# USB_C.net
KiCad netlist of a schematic drawn in Altium Designer
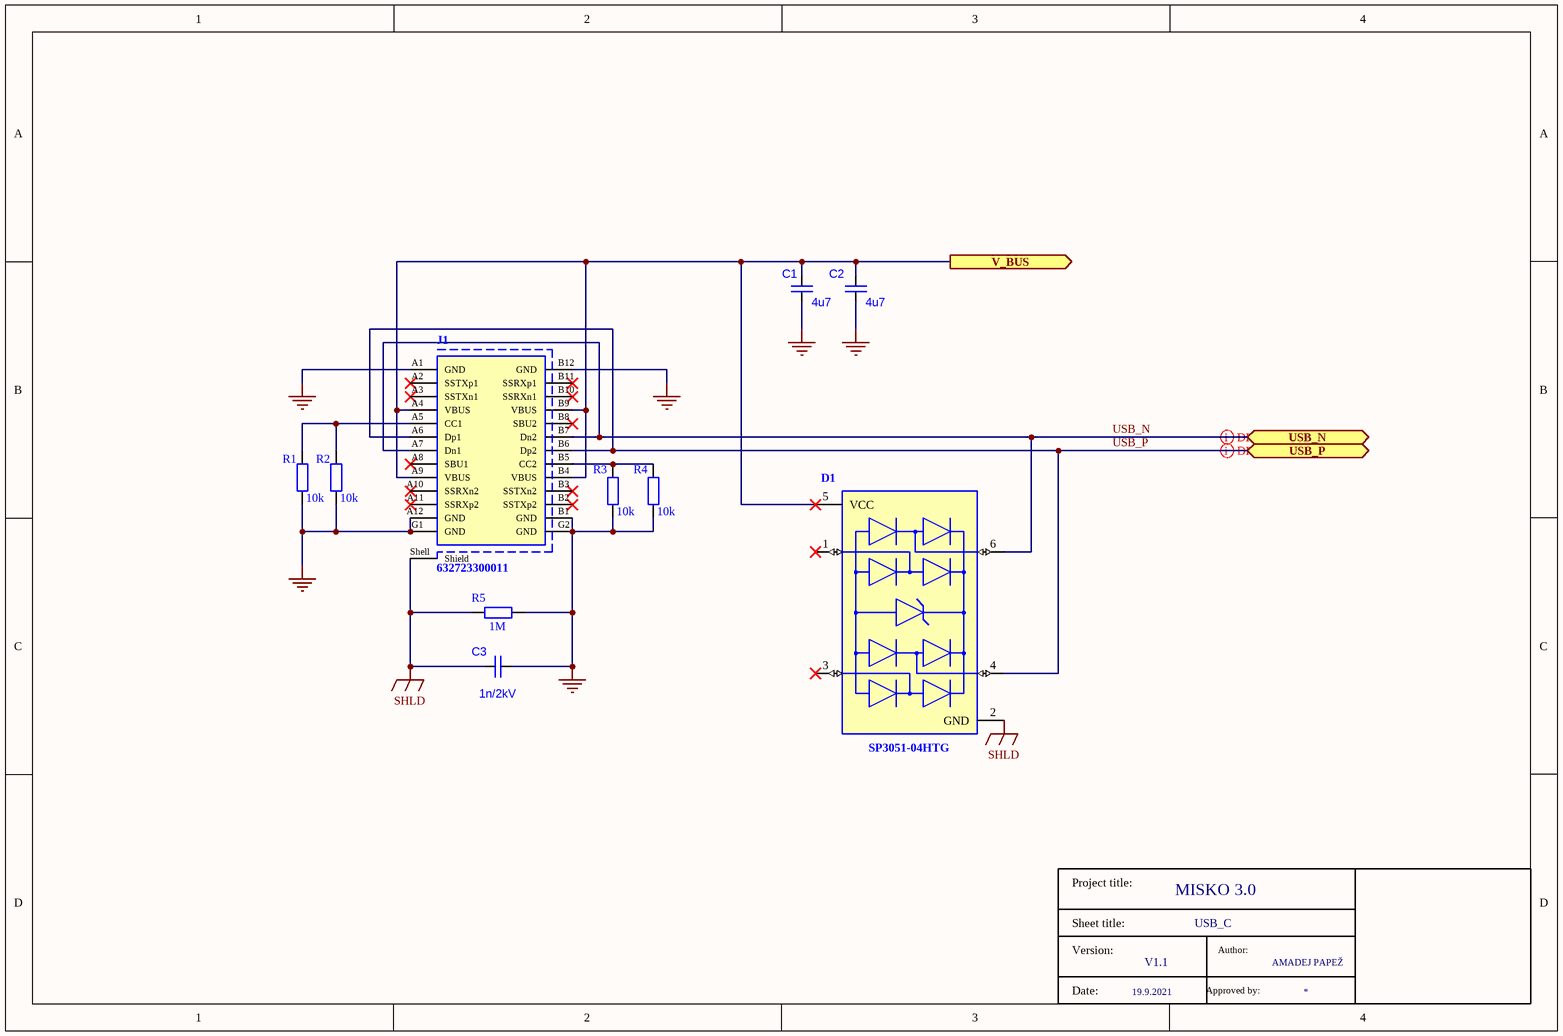
[diagram p0: USB_C.SchDoc]

(export (version "E")
  (design (tool "Eeschema 10.0.6"))
  (components
    (comp (ref "C1")
      (value "4u7")
      (footprint "C0603")
      (description "Capacitor")
      (libsource (lib "MISKO3_V6") (part "C"))
    )
    (comp (ref "C2")
      (value "4u7")
      (footprint "C0603")
      (description "Capacitor")
      (libsource (lib "MISKO3_V6") (part "C"))
    )
    (comp (ref "C3")
      (value "1n/2kV")
      (footprint "C1206")
      (description "Capacitor")
      (libsource (lib "MISKO3_V6") (part "C"))
    )
    (comp (ref "D1")
      (value "SP3051-04HTG")
      (footprint "FP-SP3051-IPC_C")
      (description "TVS DIODE 6V 17V SOT23-6")
      (fields
        (field (name "OCTOPART") "https://octopart.com/sp3051-04htg-littelfuse-29505621")
        (field (name "MANUFACTURER") "Littelfuse")
      )
      (libsource (lib "MISKO3_V6") (part "SP3051-04HTG"))
    )
    (comp (ref "J1")
      (value "632723300011")
      (footprint "632723300011")
      (description "USB 3.1 Type C Receptacle WR-COM, Horizontal, SMT / THT")
      (fields (field (name "MANUFACTURER") "Wurth Electronics") (field (name "PUBLISHER") "WurthElektronik"))
      (libsource (lib "MISKO3_V6") (part "632723300011"))
    )
    (comp (ref "R1")
      (value "10k")
      (footprint "R1608_0603I_L")
      (description "R")
      (libsource (lib "MISKO3_V6") (part "R"))
    )
    (comp (ref "R2")
      (value "10k")
      (footprint "R1608_0603I_L")
      (description "R")
      (libsource (lib "MISKO3_V6") (part "R"))
    )
    (comp (ref "R3")
      (value "10k")
      (footprint "R1608_0603I_L")
      (description "R")
      (libsource (lib "MISKO3_V6") (part "R"))
    )
    (comp (ref "R4")
      (value "10k")
      (footprint "R1608_0603I_L")
      (description "R")
      (libsource (lib "MISKO3_V6") (part "R"))
    )
    (comp (ref "R5")
      (value "1M")
      (footprint "R1608_0603I_L")
      (description "R")
      (libsource (lib "") (part "R_1"))
    )
    (comp (ref "T2") (value "~") (libsource (lib "MISKO3_V6") (part "Title block")))
  )
  (nets
    (net (code "1") (name "/USB_N") (class "Default")
      (node (ref "D1") (pin "6") (pinfunction "I/O_4_6") (pintype "bidirectional"))
      (node (ref "J1") (pin "A7") (pinfunction "Dn1_A7") (pintype "passive"))
      (node (ref "J1") (pin "B7") (pinfunction "Dn2_B7") (pintype "passive"))
    )
    (net (code "2") (name "/USB_P") (class "Default")
      (node (ref "D1") (pin "4") (pinfunction "I/O_3_4") (pintype "bidirectional"))
      (node (ref "J1") (pin "A6") (pinfunction "Dp1_A6") (pintype "passive"))
      (node (ref "J1") (pin "B6") (pinfunction "Dp2_B6") (pintype "passive"))
    )
    (net (code "3") (name "/V_BUS") (class "Default")
      (node (ref "C1") (pin "2") (pinfunction "2_2") (pintype "passive"))
      (node (ref "C2") (pin "2") (pinfunction "2_2") (pintype "passive"))
      (node (ref "D1") (pin "5") (pinfunction "VCC_5") (pintype "power_in"))
      (node (ref "J1") (pin "A4") (pinfunction "VBUS_A4") (pintype "passive"))
      (node (ref "J1") (pin "A9") (pinfunction "VBUS_A9") (pintype "passive"))
      (node (ref "J1") (pin "B4") (pinfunction "VBUS_B4") (pintype "passive"))
      (node (ref "J1") (pin "B9") (pinfunction "VBUS_B9") (pintype "passive"))
    )
    (net (code "4") (name "GND") (class "Default")
      (node (ref "C1") (pin "1") (pinfunction "1_1") (pintype "passive"))
      (node (ref "C2") (pin "1") (pinfunction "1_1") (pintype "passive"))
      (node (ref "C3") (pin "1") (pinfunction "1_1") (pintype "passive"))
      (node (ref "J1") (pin "A1") (pinfunction "GND_A1") (pintype "passive"))
      (node (ref "J1") (pin "A12") (pinfunction "GND_A12") (pintype "passive"))
      (node (ref "J1") (pin "B1") (pinfunction "GND_B1") (pintype "passive"))
      (node (ref "J1") (pin "B12") (pinfunction "GND_B12") (pintype "passive"))
      (node (ref "J1") (pin "G1") (pinfunction "GND_G1") (pintype "passive"))
      (node (ref "J1") (pin "G2") (pinfunction "GND_G2") (pintype "passive"))
      (node (ref "R1") (pin "2") (pintype "passive"))
      (node (ref "R2") (pin "2") (pintype "passive"))
      (node (ref "R3") (pin "2") (pintype "passive"))
      (node (ref "R4") (pin "2") (pintype "passive"))
      (node (ref "R5") (pin "2") (pintype "passive"))
    )
    (net (code "5") (name "Net-(J1-CC1)") (class "Default")
      (node (ref "J1") (pin "A5") (pinfunction "CC1_A5") (pintype "passive"))
      (node (ref "R1") (pin "1") (pintype "passive"))
      (node (ref "R2") (pin "1") (pintype "passive"))
    )
    (net (code "6") (name "Net-(J1-CC2)") (class "Default")
      (node (ref "J1") (pin "B5") (pinfunction "CC2_B5") (pintype "passive"))
      (node (ref "R3") (pin "1") (pintype "passive"))
      (node (ref "R4") (pin "1") (pintype "passive"))
    )
    (net (code "7") (name "SHLD") (class "Default")
      (node (ref "C3") (pin "2") (pinfunction "2_2") (pintype "passive"))
      (node (ref "D1") (pin "2") (pinfunction "GND_2") (pintype "power_in"))
      (node (ref "J1") (pin "Shell") (pinfunction "Shield_Shell") (pintype "passive"))
      (node (ref "R5") (pin "1") (pintype "passive"))
    )
    (net (code "8") (name "unconnected-(D1-I{slash}O_1-Pad1)") (class "Default")
      (node (ref "D1") (pin "1") (pinfunction "I/O_1_1") (pintype "bidirectional+no_connect"))
    )
    (net (code "9") (name "unconnected-(D1-I{slash}O_2-Pad3)") (class "Default")
      (node (ref "D1") (pin "3") (pinfunction "I/O_2_3") (pintype "bidirectional+no_connect"))
    )
    (net (code "10") (name "unconnected-(J1-SBU1-PadA8)") (class "Default")
      (node (ref "J1") (pin "A8") (pinfunction "SBU1_A8") (pintype "passive+no_connect"))
    )
    (net (code "11") (name "unconnected-(J1-SBU2-PadB8)") (class "Default")
      (node (ref "J1") (pin "B8") (pinfunction "SBU2_B8") (pintype "passive+no_connect"))
    )
    (net (code "12") (name "unconnected-(J1-SSRXn1-PadB10)") (class "Default")
      (node (ref "J1") (pin "B10") (pinfunction "SSRXn1_B10") (pintype "passive+no_connect"))
    )
    (net (code "13") (name "unconnected-(J1-SSRXn2-PadA10)") (class "Default")
      (node (ref "J1") (pin "A10") (pinfunction "SSRXn2_A10") (pintype "passive+no_connect"))
    )
    (net (code "14") (name "unconnected-(J1-SSRXp1-PadB11)") (class "Default")
      (node (ref "J1") (pin "B11") (pinfunction "SSRXp1_B11") (pintype "passive+no_connect"))
    )
    (net (code "15") (name "unconnected-(J1-SSRXp2-PadA11)") (class "Default")
      (node (ref "J1") (pin "A11") (pinfunction "SSRXp2_A11") (pintype "passive+no_connect"))
    )
    (net (code "16") (name "unconnected-(J1-SSTXn1-PadA3)") (class "Default")
      (node (ref "J1") (pin "A3") (pinfunction "SSTXn1_A3") (pintype "passive+no_connect"))
    )
    (net (code "17") (name "unconnected-(J1-SSTXn2-PadB3)") (class "Default")
      (node (ref "J1") (pin "B3") (pinfunction "SSTXn2_B3") (pintype "passive+no_connect"))
    )
    (net (code "18") (name "unconnected-(J1-SSTXp1-PadA2)") (class "Default")
      (node (ref "J1") (pin "A2") (pinfunction "SSTXp1_A2") (pintype "passive+no_connect"))
    )
    (net (code "19") (name "unconnected-(J1-SSTXp2-PadB2)") (class "Default")
      (node (ref "J1") (pin "B2") (pinfunction "SSTXp2_B2") (pintype "passive+no_connect"))
    )
  )
)
